# BV10011_ControlTopLevel.net
KiCad netlist of a schematic drawn in Altium Designer
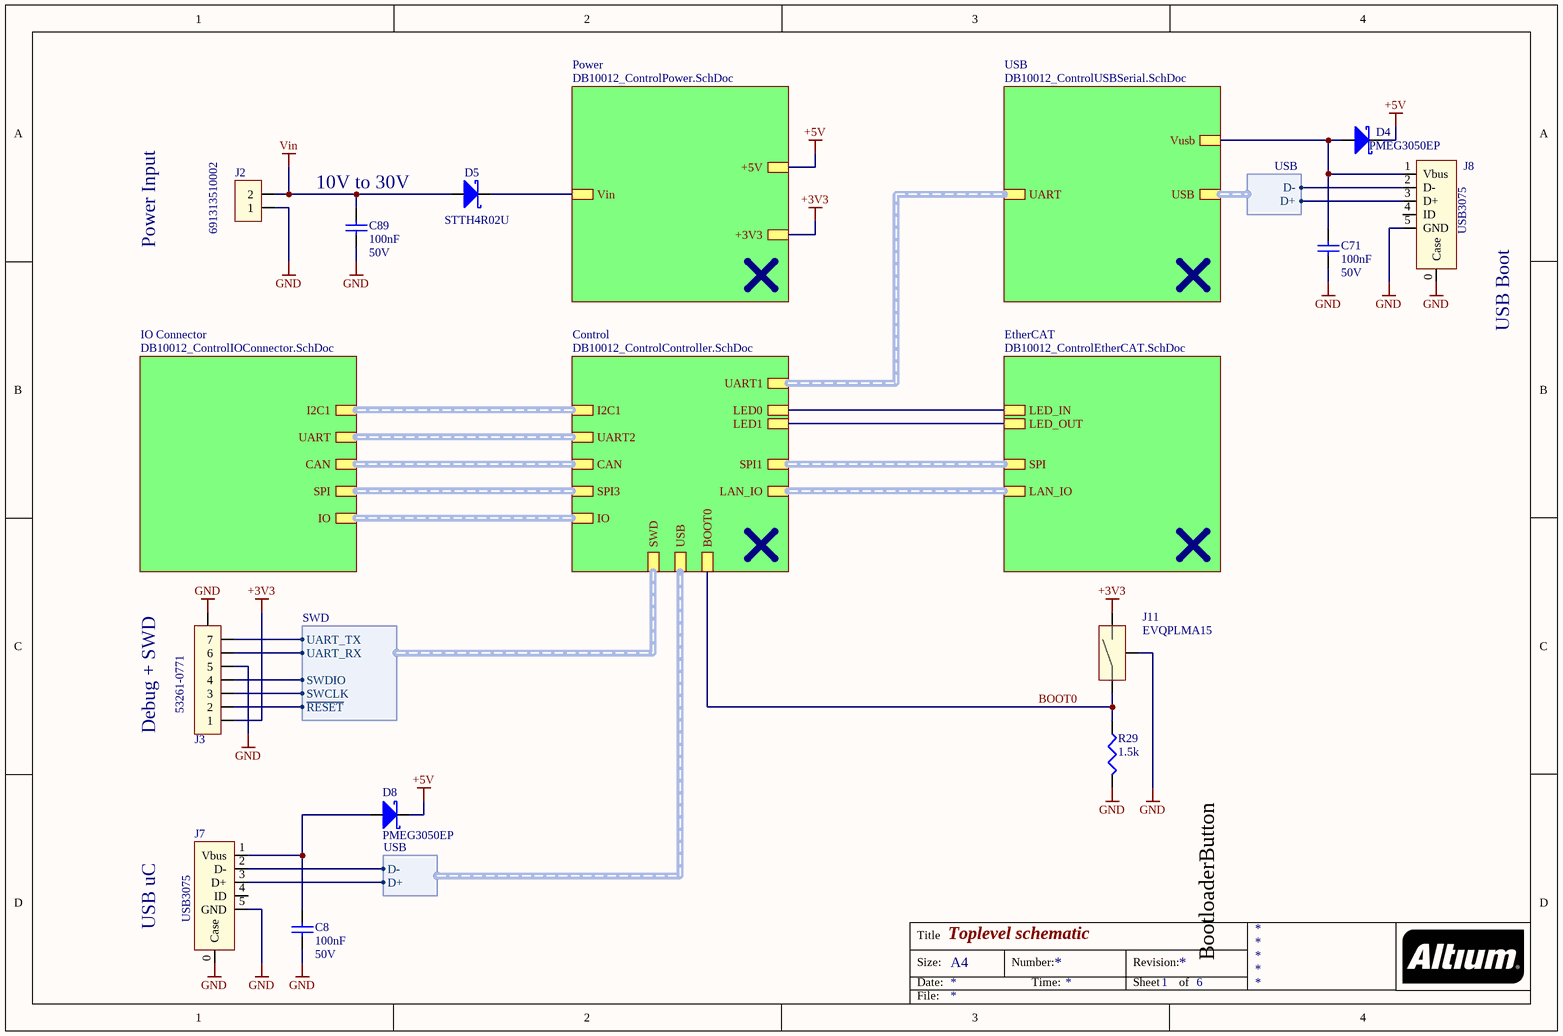
[diagram p0: BV10011_ControlTopLevel.SchDoc]

(export (version "E")
  (design (tool "Eeschema 10.0.6"))
  (components
    (comp (ref "C8")
      (value "100nF")
      (footprint "C-0805")
      (description "Capacitor, 100nF, 50V,  X7R")
      (fields (field (name "VOLTAGE RATING") "50V"))
      (libsource (lib "AR_Capacitors_Ceramic") (part "100nF/0805/CER/50V"))
    )
    (comp (ref "C71")
      (value "100nF")
      (footprint "C-0805")
      (description "Capacitor, 100nF, 50V,  X7R")
      (fields (field (name "VOLTAGE RATING") "50V"))
      (libsource (lib "AR_Capacitors_Ceramic") (part "100nF/0805/CER/50V"))
    )
    (comp (ref "C89")
      (value "100nF")
      (footprint "C-0805")
      (description "Capacitor, 100nF, 50V,  X7R")
      (fields (field (name "VOLTAGE RATING") "50V"))
      (libsource (lib "AR_Capacitors_Ceramic") (part "100nF/0805/CER/50V"))
    )
    (comp (ref "D4")
      (value "PMEG3050EP")
      (footprint "SOD128")
      (description "Diode Schottky, Vrrm: 30V, If: 3A, Vf: 0.36V")
      (libsource (lib "AR_Diodes") (part "PMEG3050EP"))
    )
    (comp (ref "D5")
      (value "STTH4R02U")
      (footprint "CASE 403A-03")
      (description "Diode Schottky, Vrrm: 200V, If: 4A, Vf: 1,05V")
      (libsource (lib "AR_Diodes") (part "STTH4R02U"))
    )
    (comp (ref "D8")
      (value "PMEG3050EP")
      (footprint "SOD128")
      (description "Diode Schottky, Vrrm: 30V, If: 3A, Vf: 0.36V")
      (libsource (lib "AR_Diodes") (part "PMEG3050EP"))
    )
    (comp (ref "J2")
      (value "691313510002")
      (footprint "691313510002")
      (description "WR-TBL 313 Series, 2 Contacts, Header, 5.08 mm")
      (libsource (lib "AR_Connectors") (part "691313510002"))
    )
    (comp (ref "J3")
      (value "53261-0771")
      (footprint "53261-0771")
      (description "PicoBlade 53261 Series, 7Pin, Right Angle")
      (libsource (lib "AR_Connectors") (part "53261-0771"))
    )
    (comp (ref "J7")
      (value "USB3075")
      (footprint "USB3075 - NOSLOT")
      (description "USB 2.0 MICRO B, RCPT, 5POS, SMT")
      (libsource (lib "AR_Connectors") (part "USB3075"))
    )
    (comp (ref "J8")
      (value "USB3075")
      (footprint "USB3075 - NOSLOT")
      (description "USB 2.0 MICRO B, RCPT, 5POS, SMT")
      (libsource (lib "") (part "USB3075_1"))
    )
    (comp (ref "J11")
      (value "EVQPLMA15")
      (footprint "EVQPLM")
      (description "SWITCH, TACT, 4.9MM, SMD, 2.6N")
      (libsource (lib "AR_Misc") (part "EVQPLMA15"))
    )
    (comp (ref "R29")
      (value "1.5k")
      (footprint "0402")
      (description "Resistor, 1.5k, 0.1%, 0.0625W, 50V, 100PPM, 0402")
      (libsource (lib "AR_Resistors_SMD") (part "1.5k/0402/0063W/50V"))
    )
  )
  (nets
    (net (code "3") (name "+3V3") (class "Default")
      (node (ref "J11") (pin "2") (pinfunction "2_2") (pintype "passive"))
      (node (ref "J3") (pin "1") (pinfunction "1_1") (pintype "passive"))
    )
    (net (code "4") (name "+5V") (class "Default")
      (node (ref "D4") (pin "2") (pinfunction "K_2") (pintype "passive"))
      (node (ref "D8") (pin "2") (pinfunction "K_2") (pintype "passive"))
    )
    (net (code "5") (name "/BOOT0") (class "Default")
      (node (ref "J11") (pin "1") (pinfunction "1_1") (pintype "passive"))
      (node (ref "R29") (pin "2") (pinfunction "2_2") (pintype "passive"))
    )
    (net (code "14") (name "/SWCLK") (class "Default")
      (node (ref "J3") (pin "3") (pinfunction "3_3") (pintype "passive"))
    )
    (net (code "15") (name "/SWDIO") (class "Default")
      (node (ref "J3") (pin "4") (pinfunction "4_4") (pintype "passive"))
    )
    (net (code "18") (name "/UART_RX") (class "Default")
      (node (ref "J3") (pin "6") (pinfunction "6_6") (pintype "passive"))
    )
    (net (code "19") (name "/UART_TX") (class "Default")
      (node (ref "J3") (pin "7") (pinfunction "7_7") (pintype "passive"))
    )
    (net (code "20") (name "/Vin") (class "Default")
      (node (ref "D5") (pin "2") (pinfunction "K_2") (pintype "passive"))
    )
    (net (code "21") (name "/Vusb") (class "Default")
      (node (ref "C71") (pin "2") (pinfunction "2_2") (pintype "passive"))
      (node (ref "D4") (pin "1") (pinfunction "A_1") (pintype "passive"))
      (node (ref "J8") (pin "1") (pinfunction "Vbus_1") (pintype "passive"))
    )
    (net (code "24") (name "/~{RESET}") (class "Default")
      (node (ref "J3") (pin "2") (pinfunction "2_2") (pintype "passive"))
    )
    (net (code "25") (name "GND") (class "Default")
      (node (ref "C71") (pin "1") (pinfunction "1_1") (pintype "passive"))
      (node (ref "C8") (pin "1") (pinfunction "1_1") (pintype "passive"))
      (node (ref "C89") (pin "1") (pinfunction "1_1") (pintype "passive"))
      (node (ref "J11") (pin "0") (pinfunction "GND_0") (pintype "passive"))
      (node (ref "J2") (pin "1") (pinfunction "1_1") (pintype "passive"))
      (node (ref "J3") (pin "0") (pinfunction "SHLD_0") (pintype "passive"))
      (node (ref "J3") (pin "5") (pinfunction "5_5") (pintype "passive"))
      (node (ref "J7") (pin "0") (pinfunction "Case_0") (pintype "passive"))
      (node (ref "J7") (pin "5") (pinfunction "GND_5") (pintype "passive"))
      (node (ref "J8") (pin "0") (pinfunction "Case_0") (pintype "passive"))
      (node (ref "J8") (pin "5") (pinfunction "GND_5") (pintype "passive"))
      (node (ref "R29") (pin "1") (pinfunction "1_1") (pintype "passive"))
    )
    (net (code "26") (name "Net-(D8-A)") (class "Default")
      (node (ref "C8") (pin "2") (pinfunction "2_2") (pintype "passive"))
      (node (ref "D8") (pin "1") (pinfunction "A_1") (pintype "passive"))
      (node (ref "J7") (pin "1") (pinfunction "Vbus_1") (pintype "passive"))
    )
    (net (code "27") (name "Vin") (class "Default")
      (node (ref "C89") (pin "2") (pinfunction "2_2") (pintype "passive"))
      (node (ref "D5") (pin "1") (pinfunction "A_1") (pintype "passive"))
      (node (ref "J2") (pin "2") (pinfunction "2_2") (pintype "passive"))
    )
    (net (code "28") (name "unconnected-(J7-D+-Pad3)") (class "Default")
      (node (ref "J7") (pin "3") (pinfunction "D+_3") (pintype "passive"))
    )
    (net (code "29") (name "unconnected-(J7-D--Pad2)") (class "Default")
      (node (ref "J7") (pin "2") (pinfunction "D-_2") (pintype "passive"))
    )
    (net (code "30") (name "unconnected-(J7-ID-Pad4)") (class "Default")
      (node (ref "J7") (pin "4") (pinfunction "ID_4") (pintype "passive"))
    )
    (net (code "31") (name "unconnected-(J8-D+-Pad3)") (class "Default")
      (node (ref "J8") (pin "3") (pinfunction "D+_3") (pintype "passive"))
    )
    (net (code "32") (name "unconnected-(J8-D--Pad2)") (class "Default")
      (node (ref "J8") (pin "2") (pinfunction "D-_2") (pintype "passive"))
    )
    (net (code "33") (name "unconnected-(J8-ID-Pad4)") (class "Default")
      (node (ref "J8") (pin "4") (pinfunction "ID_4") (pintype "passive"))
    )
  )
)
